# Geiger_Circuit.net
KiCad netlist of a schematic drawn in Altium Designer
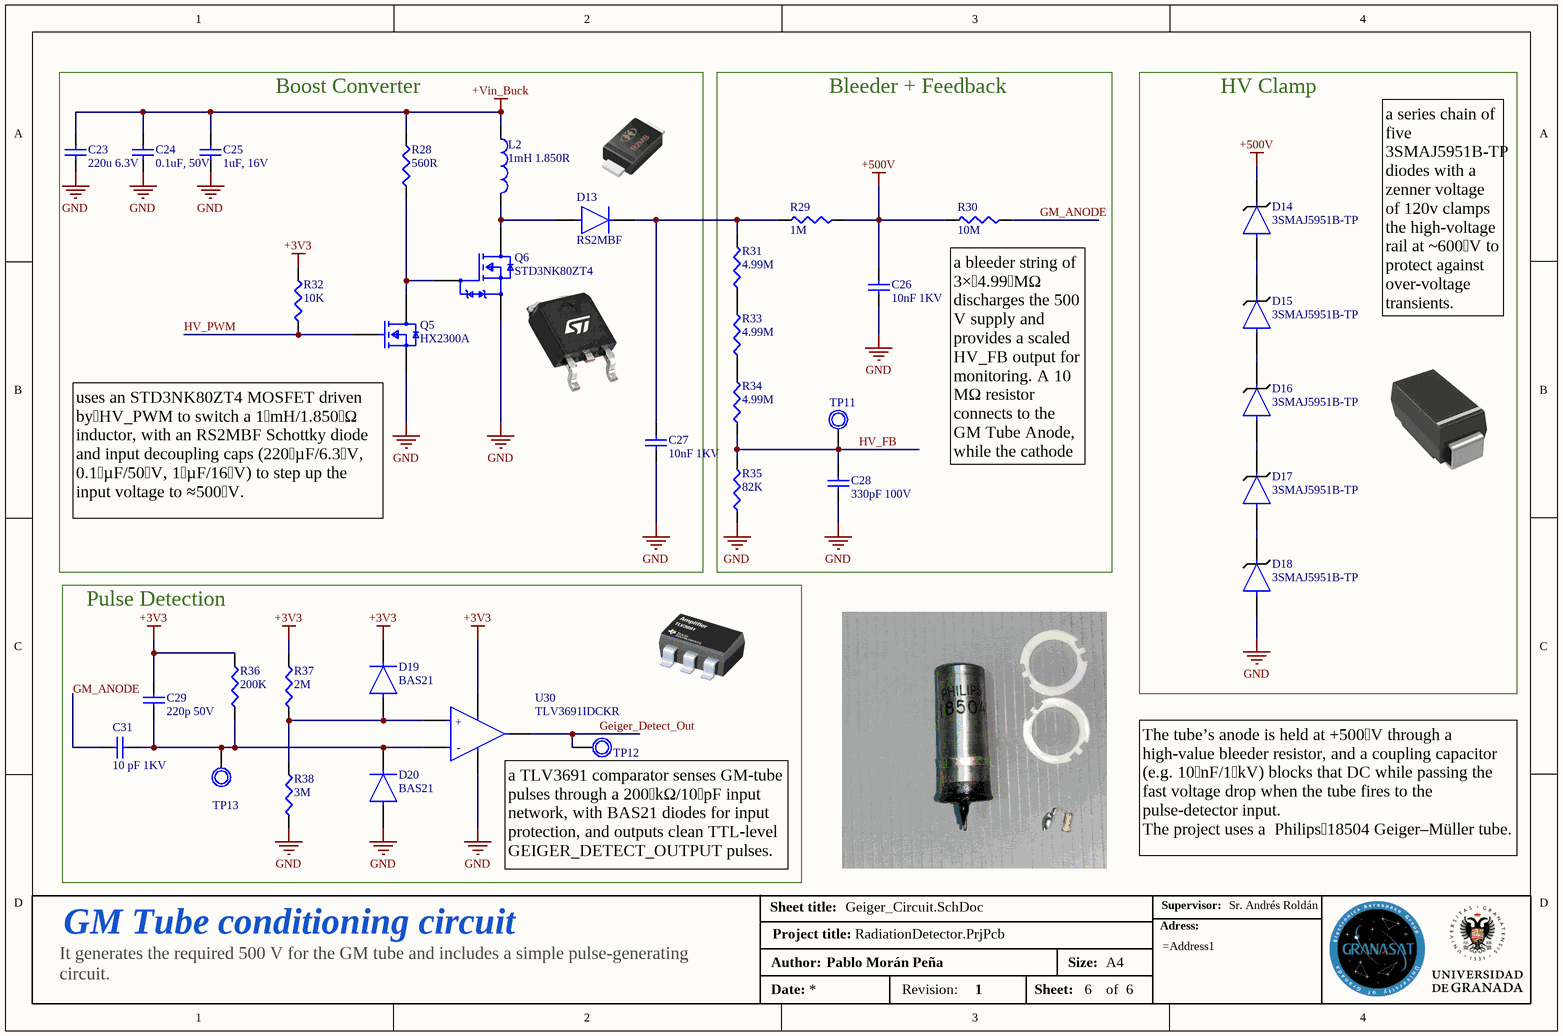
[diagram p0: Geiger_Circuit.SchDoc]

(export (version "E")
  (design (tool "Eeschema 10.0.6"))
  (components
    (comp (ref "C23")
      (value "220u 6.3V")
      (footprint "ANTC3225X280N")
      (description "CAP CER 220UF 6.3V X5R 1210")
      (fields
        (field (name "MANUFACTURER") "Samsung")
        (field (name "MANUFACTURER PART NUMBER") "CL32A227MQVNNNE")
      )
      (libsource (lib "Schlib") (part "CL32A227MQVNNNE"))
    )
    (comp (ref "C24")
      (value "0.1uF, 50V")
      (footprint "CAP 0402_1005")
      (description "CAP CER 0.1UF 50V X7R 0402")
      (fields
        (field (name "MANUFACTURER") "Samsung")
        (field (name "MANUFACTURER PART NUMBER") "CL05B104KB5NNNC")
      )
      (libsource (lib "Schlib") (part "CL05B104KB5NNNC"))
    )
    (comp (ref "C25")
      (value "1uF, 16V")
      (footprint "CAP 0402_1005")
      (description "CAP CER 1UF 16V X5R 0402")
      (fields
        (field (name "MANUFACTURER") "Samsung Electro-Mechanics")
        (field (name "MANUFACTURER PART NUMBER") "CL05A105KO5NNNC")
      )
      (libsource (lib "Schlib") (part "CL05A105KO5NNNC"))
    )
    (comp (ref "C26")
      (value "10nF 1KV")
      (footprint "CAP 1206_3216 - 1.2MM")
      (description "CAP CER 10000PF 1KV X7R 1206")
      (fields
        (field (name "MANUFACTURER") "Yageo")
        (field (name "MANUFACTURER PART NUMBER") "CC1206KKX7RCBB103")
      )
      (libsource (lib "Schlib") (part "CC1206KKX7RCBB103"))
    )
    (comp (ref "C27")
      (value "10nF 1KV")
      (footprint "CAP 1206_3216 - 1.2MM")
      (description "CAP CER 10000PF 1KV X7R 1206")
      (fields
        (field (name "MANUFACTURER") "Yageo")
        (field (name "MANUFACTURER PART NUMBER") "CC1206KKX7RCBB103")
      )
      (libsource (lib "Schlib") (part "CC1206KKX7RCBB103"))
    )
    (comp (ref "C28")
      (value "330pF 100V")
      (footprint "CAPC2012X94N")
      (description "CAP CER 330PF 100V C0G/NPO 0805")
      (fields
        (field (name "MANUFACTURER") "Yageo")
        (field (name "MANUFACTURER PART NUMBER") "CC0805JRNPO0BN331")
      )
      (libsource (lib "Schlib") (part "CC0805JRNPO0BN331"))
    )
    (comp (ref "C29")
      (value "220p 50V")
      (footprint "CAP 0402_1005")
      (description "CAP CER 220PF 50V X7R 0402")
      (fields
        (field (name "MANUFACTURER") "Samsung")
        (field (name "MANUFACTURER PART NUMBER") "CL05B221KB5NNNC")
      )
      (libsource (lib "Schlib") (part "CL05B221KB5NNNC"))
    )
    (comp (ref "C31")
      (value "10 pF 1KV")
      (footprint "CAP 1206_3216 - 1.2MM")
      (description "CAP CER 10PF 1KV C0G/NPO 1206")
      (fields
        (field (name "MANUFACTURER") "Yageo")
        (field (name "MANUFACTURER PART NUMBER") "CC1206JKNPOCBN100")
      )
      (libsource (lib "Schlib") (part "CC1206JKNPOCBN100"))
    )
    (comp (ref "D13")
      (value "RS2MBF")
      (footprint "RS2MBF")
      (description "2A 1000V 1.3V SMB-FL Diodes - General Purpose ROHS")
      (fields (field (name "LCSC PART NUMBER") "C5271853"))
      (libsource (lib "Schlib") (part "RS2MBF"))
    )
    (comp (ref "D14")
      (value "3SMAJ5951B-TP")
      (footprint "DIOM4325X244N")
      (description "DIODE ZENER 120V 3W DO214AC")
      (fields (field (name "MANUFACTURER") "MCC") (field (name "LCSC PART NUMBER") "C511105"))
      (libsource (lib "Schlib") (part "3SMAJ5951B-TP"))
    )
    (comp (ref "D15")
      (value "3SMAJ5951B-TP")
      (footprint "DIOM4325X244N")
      (description "DIODE ZENER 120V 3W DO214AC")
      (fields (field (name "MANUFACTURER") "MCC") (field (name "LCSC PART NUMBER") "C511105"))
      (libsource (lib "Schlib") (part "3SMAJ5951B-TP"))
    )
    (comp (ref "D16")
      (value "3SMAJ5951B-TP")
      (footprint "DIOM4325X244N")
      (description "DIODE ZENER 120V 3W DO214AC")
      (fields (field (name "MANUFACTURER") "MCC") (field (name "LCSC PART NUMBER") "C511105"))
      (libsource (lib "Schlib") (part "3SMAJ5951B-TP"))
    )
    (comp (ref "D17")
      (value "3SMAJ5951B-TP")
      (footprint "DIOM4325X244N")
      (description "DIODE ZENER 120V 3W DO214AC")
      (fields (field (name "MANUFACTURER") "MCC") (field (name "LCSC PART NUMBER") "C511105"))
      (libsource (lib "Schlib") (part "3SMAJ5951B-TP"))
    )
    (comp (ref "D18")
      (value "3SMAJ5951B-TP")
      (footprint "DIOM4325X244N")
      (description "DIODE ZENER 120V 3W DO214AC")
      (fields (field (name "MANUFACTURER") "MCC") (field (name "LCSC PART NUMBER") "C511105"))
      (libsource (lib "Schlib") (part "3SMAJ5951B-TP"))
    )
    (comp (ref "D19")
      (value "BAS21")
      (footprint "SOT-23")
      (description "DIODE STANDARD 250V 200MA SOT233")
      (fields (field (name "MANUFACTURER") "onsemi") (field (name "LCSC PART NUMBER") "C8661"))
      (libsource (lib "Schlib") (part "BAS21"))
    )
    (comp (ref "D20")
      (value "BAS21")
      (footprint "SOT-23")
      (description "DIODE STANDARD 250V 200MA SOT233")
      (fields (field (name "MANUFACTURER") "onsemi") (field (name "LCSC PART NUMBER") "C8661"))
      (libsource (lib "Schlib") (part "BAS21"))
    )
    (comp (ref "L2")
      (value "1mH 1.850R")
      (footprint "48102SC")
      (description "FIXED IND 1MH 520MA 1.85 OHM SMD")
      (fields (field (name "MANUFACTURER") "Murata") (field (name "MANUFACTURER PART NUMBER") "48102SC"))
      (libsource (lib "Schlib") (part "48102SC"))
    )
    (comp (ref "Q5")
      (value "HX2300A")
      (footprint "SOT-23")
      (description "20V 2.5A 46mΩ@4.5V,2.5A 650mV 1 N-channel SOT-23 MOSFETs ROHS")
      (fields (field (name "LCSC PART NUMBER") "C296302"))
      (libsource (lib "Schlib") (part "HX2300A"))
    )
    (comp (ref "Q6")
      (value "STD3NK80ZT4")
      (footprint "DPAK_STM")
      (description "MOSFET N-CH 800V 2.5A DPAK")
      (fields (field (name "MANUFACTURER") "STMicroelectronics") (field (name "LCSC PART NUMBER") "C411398"))
      (libsource (lib "Schlib") (part "STD3NK80ZT4"))
    )
    (comp (ref "R28")
      (value "560R")
      (footprint "RESC1005X37N")
      (description "RES SMD 560 OHM 1% 1/16W 0402")
      (fields
        (field (name "MANUFACTURER") "Yageo")
        (field (name "MANUFACTURER PART NUMBER") "AC0402FR-07560RL")
      )
      (libsource (lib "Schlib") (part "AC0402FR-07560RL"))
    )
    (comp (ref "R29")
      (value "1M")
      (footprint "RESC1005X37N")
      (description "RES SMD 1M OHM 1% 1/16W 0402")
      (fields
        (field (name "MANUFACTURER") "Yageo")
        (field (name "MANUFACTURER PART NUMBER") "AC0402FR-071ML")
      )
      (libsource (lib "Schlib") (part "AC0402FR-071ML"))
    )
    (comp (ref "R30")
      (value "10M")
      (footprint "RESC1005X37N")
      (description "RES SMD 10M OHM 1% 1/16W 0402")
      (fields
        (field (name "MANUFACTURER") "Yageo")
        (field (name "MANUFACTURER PART NUMBER") "AC0402FR-0710ML")
      )
      (libsource (lib "Schlib") (part "AC0402FR-0710ML"))
    )
    (comp (ref "R31")
      (value "4.99M")
      (footprint "RESC3116X65N")
      (description "RES 4.99M OHM 1% 1/4W 1206")
      (fields
        (field (name "MANUFACTURER") "Yageo")
        (field (name "MANUFACTURER PART NUMBER") "RC1206FR-074M99L")
      )
      (libsource (lib "Schlib") (part "RC1206FR-074M99L"))
    )
    (comp (ref "R32")
      (value "10K")
      (footprint "RESC1005X37N")
      (description "RES SMD 10K OHM 1% 1/16W 0402")
      (fields
        (field (name "MANUFACTURER") "Yageo")
        (field (name "MANUFACTURER PART NUMBER") "AC0402FR-0710KL")
      )
      (libsource (lib "Schlib") (part "AC0402FR-0710KL"))
    )
    (comp (ref "R33")
      (value "4.99M")
      (footprint "RESC3116X65N")
      (description "RES 4.99M OHM 1% 1/4W 1206")
      (fields
        (field (name "MANUFACTURER") "Yageo")
        (field (name "MANUFACTURER PART NUMBER") "RC1206FR-074M99L")
      )
      (libsource (lib "Schlib") (part "RC1206FR-074M99L"))
    )
    (comp (ref "R34")
      (value "4.99M")
      (footprint "RESC3116X65N")
      (description "RES 4.99M OHM 1% 1/4W 1206")
      (fields
        (field (name "MANUFACTURER") "Yageo")
        (field (name "MANUFACTURER PART NUMBER") "RC1206FR-074M99L")
      )
      (libsource (lib "Schlib") (part "RC1206FR-074M99L"))
    )
    (comp (ref "R35")
      (value "82K")
      (footprint "RESC1005X37N")
      (description "RES SMD 82K OHM 1% 1/16W 0402")
      (fields
        (field (name "MANUFACTURER") "Yageo")
        (field (name "MANUFACTURER PART NUMBER") "AC0402FR-0782KL")
      )
      (libsource (lib "Schlib") (part "AC0402FR-0782KL"))
    )
    (comp (ref "R36")
      (value "200K")
      (footprint "RESC1005X37N")
      (description "RES SMD 200K OHM 1% 1/16W 0402")
      (fields
        (field (name "MANUFACTURER") "Yageo")
        (field (name "MANUFACTURER PART NUMBER") "AC0402FR-07200KL")
      )
      (libsource (lib "Schlib") (part "AC0402FR-07200KL"))
    )
    (comp (ref "R37")
      (value "2M")
      (footprint "RESC1005X37N")
      (description "RES SMD 2M OHM 1% 1/16W 0402")
      (fields
        (field (name "MANUFACTURER") "Yageo")
        (field (name "MANUFACTURER PART NUMBER") "AC0402FR-072ML")
      )
      (libsource (lib "Schlib") (part "AC0402FR-072ML"))
    )
    (comp (ref "R38")
      (value "3M")
      (footprint "RESC1005X37N")
      (description "RES SMD 3M OHM 5% 1/16W 0402")
      (fields
        (field (name "MANUFACTURER") "Yageo")
        (field (name "MANUFACTURER PART NUMBER") "AC0402JR-073ML")
      )
      (libsource (lib "Schlib") (part "AC0402JR-073ML"))
    )
    (comp (ref "TP11")
      (value "Testpoint")
      (footprint "Testpoint")
      (libsource (lib "Schlib") (part "Testpoint"))
    )
    (comp (ref "TP12")
      (value "Testpoint")
      (footprint "Testpoint")
      (libsource (lib "Schlib") (part "Testpoint"))
    )
    (comp (ref "TP13")
      (value "Testpoint")
      (footprint "Testpoint")
      (libsource (lib "Schlib") (part "Testpoint"))
    )
    (comp (ref "U30")
      (value "TLV3691IDCKR")
      (footprint "FP-DCK0005A-IPC_B")
      (description "IC COMPARATOR 1 GEN PUR SC70-5")
      (fields (field (name "MANUFACTURER") "Texas Instruments") (field (name "LCSC PART NUMBER") "C180352"))
      (libsource (lib "Schlib") (part "TLV3691IDCKR"))
    )
  )
  (nets
    (net (code "1") (name "+3V3") (class "Default")
      (node (ref "C29") (pin "2") (pinfunction "2_2") (pintype "passive"))
      (node (ref "D19") (pin "3") (pinfunction "C_3") (pintype "passive"))
      (node (ref "R32") (pin "2") (pinfunction "2_2") (pintype "passive"))
      (node (ref "R36") (pin "2") (pinfunction "2_2") (pintype "passive"))
      (node (ref "R37") (pin "1") (pinfunction "1_1") (pintype "passive"))
      (node (ref "U30") (pin "5") (pinfunction "VCC_5") (pintype "power_in"))
    )
    (net (code "2") (name "+500V") (class "Default")
      (node (ref "C26") (pin "2") (pinfunction "2_2") (pintype "passive"))
      (node (ref "D14") (pin "1") (pinfunction "C_1") (pintype "passive"))
      (node (ref "R29") (pin "2") (pinfunction "2_2") (pintype "passive"))
      (node (ref "R30") (pin "1") (pinfunction "1_1") (pintype "passive"))
    )
    (net (code "3") (name "+Vin_Buck") (class "Default")
      (node (ref "C23") (pin "2") (pinfunction "2_2") (pintype "passive"))
      (node (ref "C24") (pin "2") (pinfunction "2_2") (pintype "passive"))
      (node (ref "C25") (pin "2") (pinfunction "2_2") (pintype "passive"))
      (node (ref "L2") (pin "1") (pinfunction "1_1") (pintype "passive"))
      (node (ref "R28") (pin "2") (pinfunction "2_2") (pintype "passive"))
    )
    (net (code "4") (name "/GM_ANODE") (class "Default")
      (node (ref "C31") (pin "1") (pinfunction "1_1") (pintype "passive"))
      (node (ref "R30") (pin "2") (pinfunction "2_2") (pintype "passive"))
    )
    (net (code "5") (name "/Geiger_Detect_Out") (class "Default")
      (node (ref "TP12") (pin "1") (pinfunction "1_1") (pintype "passive"))
      (node (ref "U30") (pin "4") (pinfunction "OUT_4") (pintype "passive"))
    )
    (net (code "6") (name "/HV_FB") (class "Default")
      (node (ref "C28") (pin "2") (pinfunction "2_2") (pintype "passive"))
      (node (ref "R34") (pin "2") (pinfunction "2_2") (pintype "passive"))
      (node (ref "R35") (pin "2") (pinfunction "2_2") (pintype "passive"))
      (node (ref "TP11") (pin "1") (pinfunction "1_1") (pintype "passive"))
    )
    (net (code "7") (name "/HV_PWM") (class "Default")
      (node (ref "Q5") (pin "1") (pinfunction "G_1") (pintype "passive"))
      (node (ref "R32") (pin "1") (pinfunction "1_1") (pintype "passive"))
    )
    (net (code "8") (name "GND") (class "Default")
      (node (ref "C23") (pin "1") (pinfunction "1_1") (pintype "passive"))
      (node (ref "C24") (pin "1") (pinfunction "1_1") (pintype "passive"))
      (node (ref "C25") (pin "1") (pinfunction "1_1") (pintype "passive"))
      (node (ref "C26") (pin "1") (pinfunction "1_1") (pintype "passive"))
      (node (ref "C27") (pin "1") (pinfunction "1_1") (pintype "passive"))
      (node (ref "C28") (pin "1") (pinfunction "1_1") (pintype "passive"))
      (node (ref "D18") (pin "2") (pinfunction "A_2") (pintype "passive"))
      (node (ref "D20") (pin "1") (pinfunction "A_1") (pintype "passive"))
      (node (ref "Q5") (pin "2") (pinfunction "S_2") (pintype "passive"))
      (node (ref "Q6") (pin "3") (pinfunction "Source_3") (pintype "passive"))
      (node (ref "R35") (pin "1") (pinfunction "1_1") (pintype "passive"))
      (node (ref "R38") (pin "1") (pinfunction "1_1") (pintype "passive"))
      (node (ref "U30") (pin "2") (pinfunction "GND_2") (pintype "power_in"))
    )
    (net (code "9") (name "Net-(D13-A)") (class "Default")
      (node (ref "D13") (pin "2") (pinfunction "A_2") (pintype "passive"))
      (node (ref "L2") (pin "2") (pinfunction "2_2") (pintype "passive"))
      (node (ref "Q6") (pin "2") (pinfunction "Drain_2") (pintype "passive"))
    )
    (net (code "10") (name "Net-(D13-C)") (class "Default")
      (node (ref "C27") (pin "2") (pinfunction "2_2") (pintype "passive"))
      (node (ref "D13") (pin "1") (pinfunction "C_1") (pintype "passive"))
      (node (ref "R29") (pin "1") (pinfunction "1_1") (pintype "passive"))
      (node (ref "R31") (pin "1") (pinfunction "1_1") (pintype "passive"))
    )
    (net (code "11") (name "Net-(D14-A)") (class "Default")
      (node (ref "D14") (pin "2") (pinfunction "A_2") (pintype "passive"))
      (node (ref "D15") (pin "1") (pinfunction "C_1") (pintype "passive"))
    )
    (net (code "12") (name "Net-(D15-A)") (class "Default")
      (node (ref "D15") (pin "2") (pinfunction "A_2") (pintype "passive"))
      (node (ref "D16") (pin "1") (pinfunction "C_1") (pintype "passive"))
    )
    (net (code "13") (name "Net-(D16-A)") (class "Default")
      (node (ref "D16") (pin "2") (pinfunction "A_2") (pintype "passive"))
      (node (ref "D17") (pin "1") (pinfunction "C_1") (pintype "passive"))
    )
    (net (code "14") (name "Net-(D17-A)") (class "Default")
      (node (ref "D17") (pin "2") (pinfunction "A_2") (pintype "passive"))
      (node (ref "D18") (pin "1") (pinfunction "C_1") (pintype "passive"))
    )
    (net (code "15") (name "Net-(D19-A)") (class "Default")
      (node (ref "D19") (pin "1") (pinfunction "A_1") (pintype "passive"))
      (node (ref "R37") (pin "2") (pinfunction "2_2") (pintype "passive"))
      (node (ref "R38") (pin "2") (pinfunction "2_2") (pintype "passive"))
      (node (ref "U30") (pin "1") (pinfunction "IN+_1") (pintype "tri_state"))
    )
    (net (code "16") (name "Net-(D20-C)") (class "Default")
      (node (ref "C29") (pin "1") (pinfunction "1_1") (pintype "passive"))
      (node (ref "C31") (pin "2") (pinfunction "2_2") (pintype "passive"))
      (node (ref "D20") (pin "3") (pinfunction "C_3") (pintype "passive"))
      (node (ref "R36") (pin "1") (pinfunction "1_1") (pintype "passive"))
      (node (ref "TP13") (pin "1") (pinfunction "1_1") (pintype "passive"))
      (node (ref "U30") (pin "3") (pinfunction "IN-_3") (pintype "tri_state"))
    )
    (net (code "17") (name "Net-(Q5-D)") (class "Default")
      (node (ref "Q5") (pin "3") (pinfunction "D_3") (pintype "passive"))
      (node (ref "Q6") (pin "1") (pinfunction "Gate_1") (pintype "passive"))
      (node (ref "R28") (pin "1") (pinfunction "1_1") (pintype "passive"))
    )
    (net (code "18") (name "Net-(R31-Pad2)") (class "Default")
      (node (ref "R31") (pin "2") (pinfunction "2_2") (pintype "passive"))
      (node (ref "R33") (pin "1") (pinfunction "1_1") (pintype "passive"))
    )
    (net (code "19") (name "Net-(R33-Pad2)") (class "Default")
      (node (ref "R33") (pin "2") (pinfunction "2_2") (pintype "passive"))
      (node (ref "R34") (pin "1") (pinfunction "1_1") (pintype "passive"))
    )
  )
)
